# Sheet3.net
KiCad netlist of a schematic drawn in Altium Designer
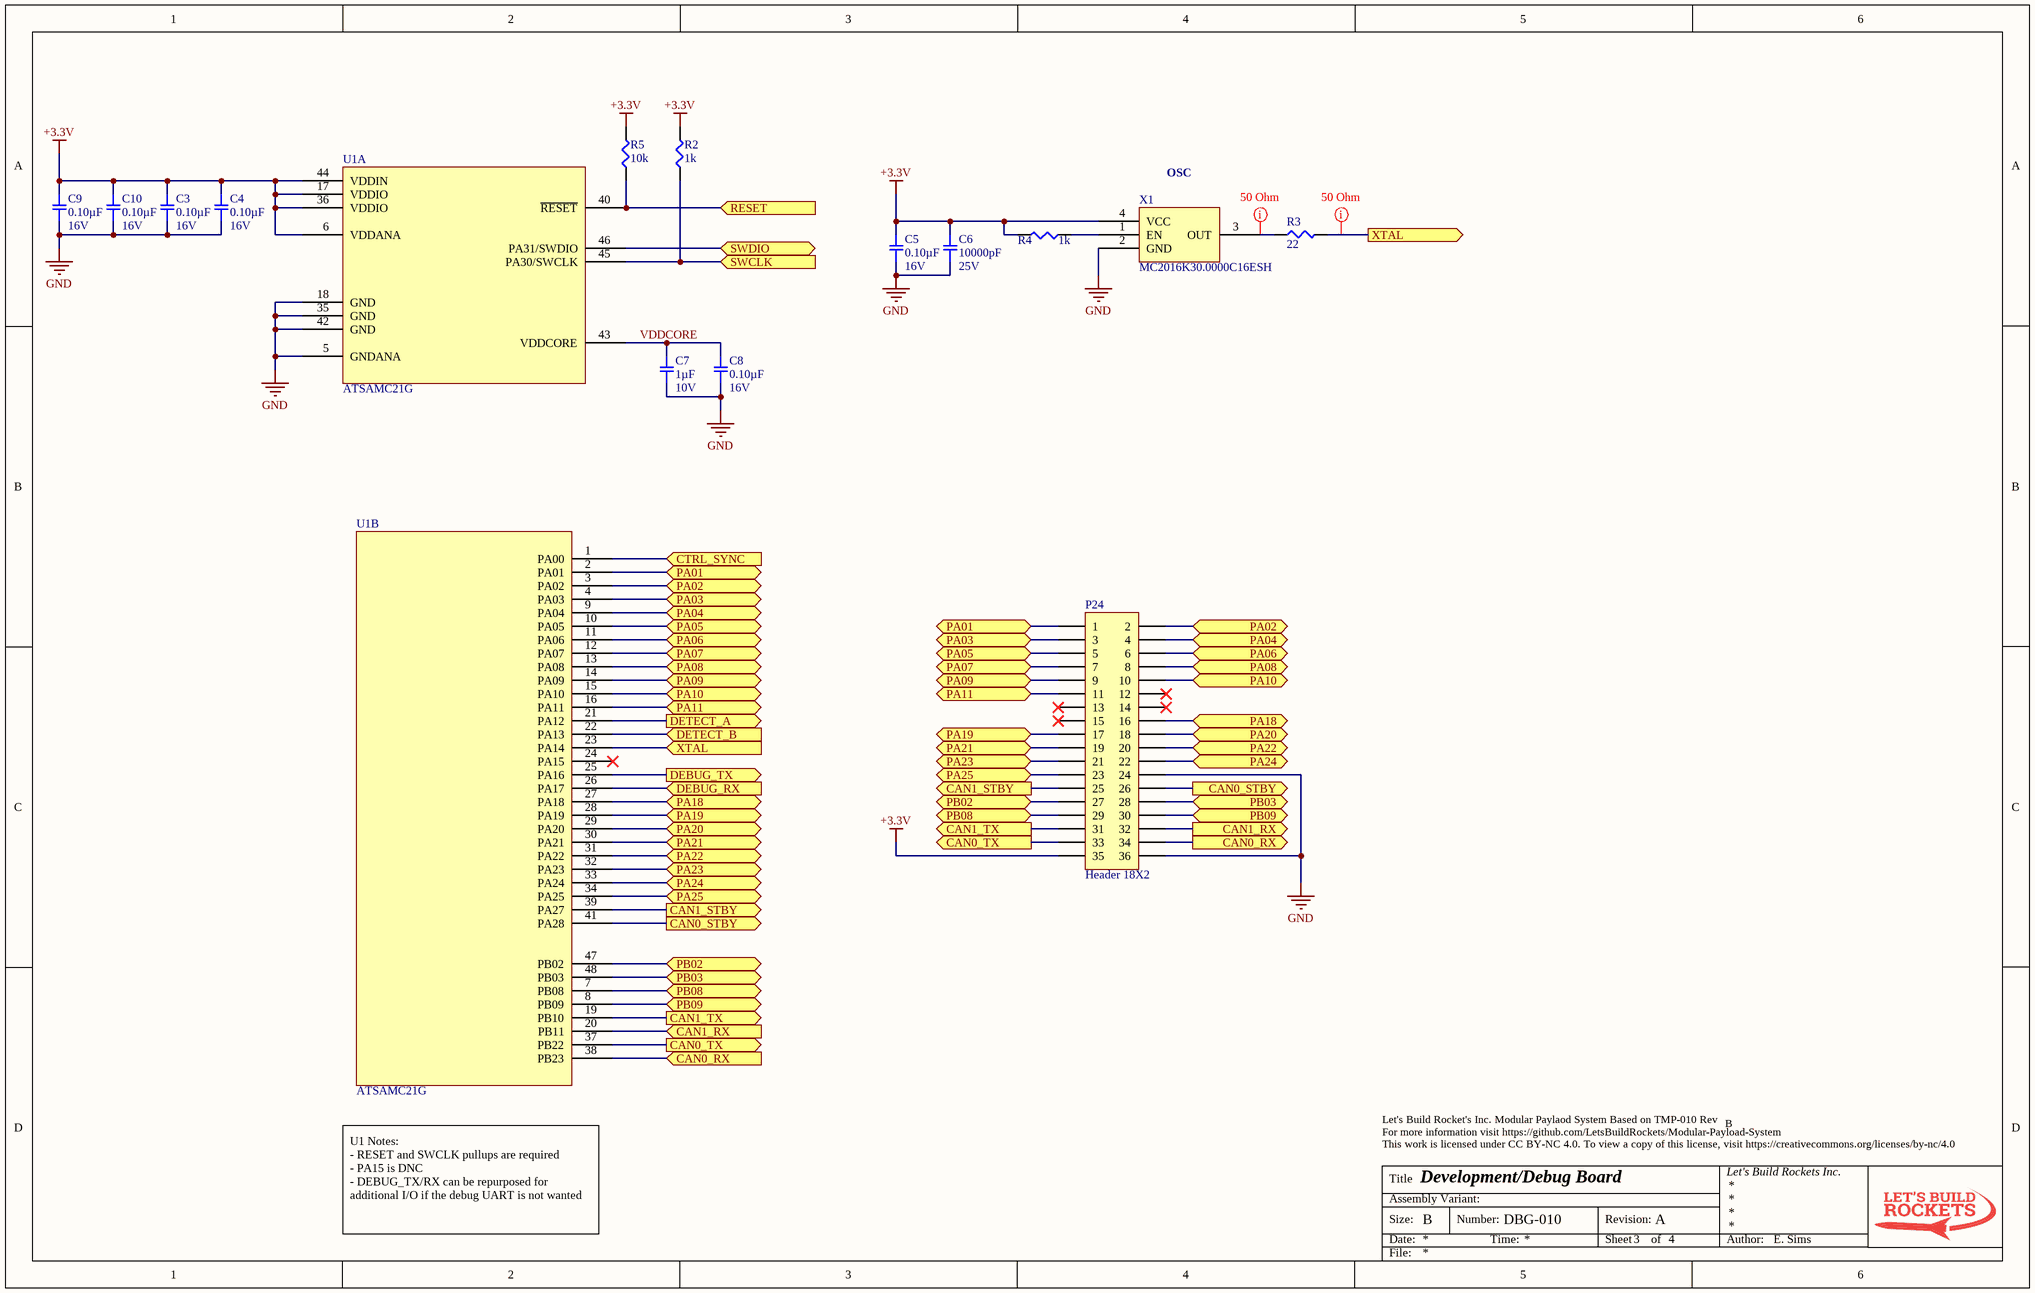
[diagram p0: Sheet3.SchDoc]

(export (version "E")
  (design (tool "Eeschema 10.0.6"))
  (components
    (comp (ref "C3")
      (value "0.10µF")
      (footprint "SMD-0402C")
      (description "CAP CER 0.1UF 16V X7R 0402")
      (fields
        (field (name "DIGI-KEY PART NUMBER") "490-4759-1-ND")
        (field (name "PART NUMBER") "GCM155R71C104KA55D")
        (field (name "VOLTAGE") "16V")
      )
      (libsource (lib "capacitor_murata_0402") (part "GCM155R71C104KA55D"))
    )
    (comp (ref "C4")
      (value "0.10µF")
      (footprint "SMD-0402C")
      (description "CAP CER 0.1UF 16V X7R 0402")
      (fields
        (field (name "DIGI-KEY PART NUMBER") "490-4759-1-ND")
        (field (name "PART NUMBER") "GCM155R71C104KA55D")
        (field (name "VOLTAGE") "16V")
      )
      (libsource (lib "capacitor_murata_0402") (part "GCM155R71C104KA55D"))
    )
    (comp (ref "C5")
      (value "0.10µF")
      (footprint "SMD-0402C")
      (description "CAP CER 0.1UF 16V X7R 0402")
      (fields
        (field (name "DIGI-KEY PART NUMBER") "490-4759-1-ND")
        (field (name "PART NUMBER") "GCM155R71C104KA55D")
        (field (name "VOLTAGE") "16V")
      )
      (libsource (lib "capacitor_murata_0402") (part "GCM155R71C104KA55D"))
    )
    (comp (ref "C6")
      (value "10000pF")
      (footprint "SMD-0402C")
      (description "CAP CER 10000PF 25V X7R 0402")
      (fields
        (field (name "DIGI-KEY PART NUMBER") "490-6043-1-ND")
        (field (name "PART NUMBER") "GCM155R71E103KA37D")
        (field (name "VOLTAGE") "25V")
      )
      (libsource (lib "capacitor_murata_0402") (part "GCM155R71E103KA37D"))
    )
    (comp (ref "C7")
      (value "1µF")
      (footprint "SMD-0402C")
      (description "CAP CER 1UF 10V X7S 0402")
      (fields
        (field (name "DIGI-KEY PART NUMBER") "490-13409-1-ND")
        (field (name "PART NUMBER") "GCM155C71A105KE38D")
        (field (name "VOLTAGE") "10V")
      )
      (libsource (lib "capacitor_murata_0402") (part "GCM155C71A105KE38D"))
    )
    (comp (ref "C8")
      (value "0.10µF")
      (footprint "SMD-0402C")
      (description "CAP CER 0.1UF 16V X7R 0402")
      (fields
        (field (name "DIGI-KEY PART NUMBER") "490-4759-1-ND")
        (field (name "PART NUMBER") "GCM155R71C104KA55D")
        (field (name "VOLTAGE") "16V")
      )
      (libsource (lib "capacitor_murata_0402") (part "GCM155R71C104KA55D"))
    )
    (comp (ref "C9")
      (value "0.10µF")
      (footprint "SMD-0402C")
      (description "CAP CER 0.1UF 16V X7R 0402")
      (fields
        (field (name "DIGI-KEY PART NUMBER") "490-4759-1-ND")
        (field (name "PART NUMBER") "GCM155R71C104KA55D")
        (field (name "VOLTAGE") "16V")
      )
      (libsource (lib "capacitor_murata_0402") (part "GCM155R71C104KA55D"))
    )
    (comp (ref "C10")
      (value "0.10µF")
      (footprint "SMD-0402C")
      (description "CAP CER 0.1UF 16V X7R 0402")
      (fields
        (field (name "DIGI-KEY PART NUMBER") "490-4759-1-ND")
        (field (name "PART NUMBER") "GCM155R71C104KA55D")
        (field (name "VOLTAGE") "16V")
      )
      (libsource (lib "capacitor_murata_0402") (part "GCM155R71C104KA55D"))
    )
    (comp (ref "P24")
      (value "Header 18X2")
      (footprint "HDR2X18")
      (description "Header, 18-Pin, Dual row")
      (fields (field (name "PUBLISHER") "Altium Limited"))
      (libsource (lib "Miscellaneous Connectors") (part "Header 18X2"))
    )
    (comp (ref "R2")
      (value "1k")
      (footprint "SMD-0402-RES")
      (description "RES SMD 1K OHM 5% 1/10W 0402")
      (fields (field (name "PART NUMBER") "ERJ-2GEJ102X") (field (name "DIGI-KEY PART NUMBER") "P1.0KJCT-ND"))
      (libsource (lib "Panasonic_ERJ_0402") (part "ERJ-2GEJ102X"))
    )
    (comp (ref "R3")
      (value "22")
      (footprint "SMD-0402-RES")
      (description "RES SMD 22 OHM 1% 1/10W 0402")
      (fields
        (field (name "PART NUMBER") "ERJ-2RKF22R0X")
        (field (name "DIGI-KEY PART NUMBER") "P22.0LCT-ND")
      )
      (libsource (lib "Panasonic_ERJ_0402") (part "ERJ-2RKF22R0X"))
    )
    (comp (ref "R4")
      (value "1k")
      (footprint "SMD-0402-RES")
      (description "RES SMD 1K OHM 5% 1/10W 0402")
      (fields (field (name "PART NUMBER") "ERJ-2GEJ102X") (field (name "DIGI-KEY PART NUMBER") "P1.0KJCT-ND"))
      (libsource (lib "Panasonic_ERJ_0402") (part "ERJ-2GEJ102X"))
    )
    (comp (ref "R5")
      (value "10k")
      (footprint "SMD-0402-RES")
      (description "RES SMD 10K OHM 5% 1/10W 0402")
      (fields (field (name "PART NUMBER") "ERJ-2GEJ103X") (field (name "DIGI-KEY PART NUMBER") "P10KJCT-ND"))
      (libsource (lib "Panasonic_ERJ_0402") (part "ERJ-2GEJ103X"))
    )
    (comp (ref "U1")
      (value "ATSAMC21G")
      (footprint "TSQFP50P900X900X120-48N")
      (libsource (lib "ModularPayload") (part "ATSAMC21G"))
    )
    (comp (ref "X1")
      (value "MC2016K30.0000C16ESH")
      (footprint "MC2016")
      (libsource (lib "ModularPayload") (part "MC2016K30.0000C16ESH"))
    )
  )
  (nets
    (net (code "1") (name "+3.3V") (class "Default")
      (node (ref "C10") (pin "2") (pinfunction "2_2") (pintype "passive"))
      (node (ref "C3") (pin "2") (pinfunction "2_2") (pintype "passive"))
      (node (ref "C4") (pin "2") (pinfunction "2_2") (pintype "passive"))
      (node (ref "C5") (pin "2") (pinfunction "2_2") (pintype "passive"))
      (node (ref "C6") (pin "2") (pinfunction "2_2") (pintype "passive"))
      (node (ref "C9") (pin "2") (pinfunction "2_2") (pintype "passive"))
      (node (ref "P24") (pin "35") (pinfunction "35_35") (pintype "passive"))
      (node (ref "R2") (pin "2") (pinfunction "2_2") (pintype "passive"))
      (node (ref "R4") (pin "2") (pinfunction "2_2") (pintype "passive"))
      (node (ref "R5") (pin "2") (pinfunction "2_2") (pintype "passive"))
      (node (ref "U1") (pin "17") (pinfunction "VDDIO_17") (pintype "passive"))
      (node (ref "U1") (pin "36") (pinfunction "VDDIO_36") (pintype "passive"))
      (node (ref "U1") (pin "44") (pinfunction "VDDIN_44") (pintype "passive"))
      (node (ref "U1") (pin "6") (pinfunction "VDDANA_6") (pintype "passive"))
      (node (ref "X1") (pin "4") (pinfunction "VCC_4") (pintype "passive"))
    )
    (net (code "2") (name "/CAN0_RX") (class "Default")
      (node (ref "P24") (pin "34") (pinfunction "34_34") (pintype "passive"))
      (node (ref "U1") (pin "38") (pinfunction "PB23_38") (pintype "passive"))
    )
    (net (code "3") (name "/CAN0_STBY") (class "Default")
      (node (ref "P24") (pin "26") (pinfunction "26_26") (pintype "passive"))
      (node (ref "U1") (pin "41") (pinfunction "PA28_41") (pintype "passive"))
    )
    (net (code "4") (name "/CAN0_TX") (class "Default")
      (node (ref "P24") (pin "33") (pinfunction "33_33") (pintype "passive"))
      (node (ref "U1") (pin "37") (pinfunction "PB22_37") (pintype "passive"))
    )
    (net (code "5") (name "/CAN1_RX") (class "Default")
      (node (ref "P24") (pin "32") (pinfunction "32_32") (pintype "passive"))
      (node (ref "U1") (pin "20") (pinfunction "PB11_20") (pintype "passive"))
    )
    (net (code "6") (name "/CAN1_STBY") (class "Default")
      (node (ref "P24") (pin "25") (pinfunction "25_25") (pintype "passive"))
      (node (ref "U1") (pin "39") (pinfunction "PA27_39") (pintype "passive"))
    )
    (net (code "7") (name "/CAN1_TX") (class "Default")
      (node (ref "P24") (pin "31") (pinfunction "31_31") (pintype "passive"))
      (node (ref "U1") (pin "19") (pinfunction "PB10_19") (pintype "passive"))
    )
    (net (code "8") (name "/CTRL_SYNC") (class "Default")
      (node (ref "U1") (pin "1") (pinfunction "PA00_1") (pintype "passive"))
    )
    (net (code "9") (name "/DEBUG_RX") (class "Default")
      (node (ref "U1") (pin "26") (pinfunction "PA17_26") (pintype "passive"))
    )
    (net (code "10") (name "/DEBUG_TX") (class "Default")
      (node (ref "U1") (pin "25") (pinfunction "PA16_25") (pintype "passive"))
    )
    (net (code "11") (name "/DETECT_A") (class "Default")
      (node (ref "U1") (pin "21") (pinfunction "PA12_21") (pintype "passive"))
    )
    (net (code "12") (name "/DETECT_B") (class "Default")
      (node (ref "U1") (pin "22") (pinfunction "PA13_22") (pintype "passive"))
    )
    (net (code "13") (name "/PA01") (class "Default")
      (node (ref "P24") (pin "1") (pinfunction "1_1") (pintype "passive"))
      (node (ref "U1") (pin "2") (pinfunction "PA01_2") (pintype "passive"))
    )
    (net (code "14") (name "/PA02") (class "Default")
      (node (ref "P24") (pin "2") (pinfunction "2_2") (pintype "passive"))
      (node (ref "U1") (pin "3") (pinfunction "PA02_3") (pintype "passive"))
    )
    (net (code "15") (name "/PA03") (class "Default")
      (node (ref "P24") (pin "3") (pinfunction "3_3") (pintype "passive"))
      (node (ref "U1") (pin "4") (pinfunction "PA03_4") (pintype "passive"))
    )
    (net (code "16") (name "/PA04") (class "Default")
      (node (ref "P24") (pin "4") (pinfunction "4_4") (pintype "passive"))
      (node (ref "U1") (pin "9") (pinfunction "PA04_9") (pintype "passive"))
    )
    (net (code "17") (name "/PA05") (class "Default")
      (node (ref "P24") (pin "5") (pinfunction "5_5") (pintype "passive"))
      (node (ref "U1") (pin "10") (pinfunction "PA05_10") (pintype "passive"))
    )
    (net (code "18") (name "/PA06") (class "Default")
      (node (ref "P24") (pin "6") (pinfunction "6_6") (pintype "passive"))
      (node (ref "U1") (pin "11") (pinfunction "PA06_11") (pintype "passive"))
    )
    (net (code "19") (name "/PA07") (class "Default")
      (node (ref "P24") (pin "7") (pinfunction "7_7") (pintype "passive"))
      (node (ref "U1") (pin "12") (pinfunction "PA07_12") (pintype "passive"))
    )
    (net (code "20") (name "/PA08") (class "Default")
      (node (ref "P24") (pin "8") (pinfunction "8_8") (pintype "passive"))
      (node (ref "U1") (pin "13") (pinfunction "PA08_13") (pintype "passive"))
    )
    (net (code "21") (name "/PA09") (class "Default")
      (node (ref "P24") (pin "9") (pinfunction "9_9") (pintype "passive"))
      (node (ref "U1") (pin "14") (pinfunction "PA09_14") (pintype "passive"))
    )
    (net (code "22") (name "/PA10") (class "Default")
      (node (ref "P24") (pin "10") (pinfunction "10_10") (pintype "passive"))
      (node (ref "U1") (pin "15") (pinfunction "PA10_15") (pintype "passive"))
    )
    (net (code "23") (name "/PA11") (class "Default")
      (node (ref "P24") (pin "11") (pinfunction "11_11") (pintype "passive"))
      (node (ref "U1") (pin "16") (pinfunction "PA11_16") (pintype "passive"))
    )
    (net (code "24") (name "/PA18") (class "Default")
      (node (ref "P24") (pin "16") (pinfunction "16_16") (pintype "passive"))
      (node (ref "U1") (pin "27") (pinfunction "PA18_27") (pintype "passive"))
    )
    (net (code "25") (name "/PA19") (class "Default")
      (node (ref "P24") (pin "17") (pinfunction "17_17") (pintype "passive"))
      (node (ref "U1") (pin "28") (pinfunction "PA19_28") (pintype "passive"))
    )
    (net (code "26") (name "/PA20") (class "Default")
      (node (ref "P24") (pin "18") (pinfunction "18_18") (pintype "passive"))
      (node (ref "U1") (pin "29") (pinfunction "PA20_29") (pintype "passive"))
    )
    (net (code "27") (name "/PA21") (class "Default")
      (node (ref "P24") (pin "19") (pinfunction "19_19") (pintype "passive"))
      (node (ref "U1") (pin "30") (pinfunction "PA21_30") (pintype "passive"))
    )
    (net (code "28") (name "/PA22") (class "Default")
      (node (ref "P24") (pin "20") (pinfunction "20_20") (pintype "passive"))
      (node (ref "U1") (pin "31") (pinfunction "PA22_31") (pintype "passive"))
    )
    (net (code "29") (name "/PA23") (class "Default")
      (node (ref "P24") (pin "21") (pinfunction "21_21") (pintype "passive"))
      (node (ref "U1") (pin "32") (pinfunction "PA23_32") (pintype "passive"))
    )
    (net (code "30") (name "/PA24") (class "Default")
      (node (ref "P24") (pin "22") (pinfunction "22_22") (pintype "passive"))
      (node (ref "U1") (pin "33") (pinfunction "PA24_33") (pintype "passive"))
    )
    (net (code "31") (name "/PA25") (class "Default")
      (node (ref "P24") (pin "23") (pinfunction "23_23") (pintype "passive"))
      (node (ref "U1") (pin "34") (pinfunction "PA25_34") (pintype "passive"))
    )
    (net (code "32") (name "/PB02") (class "Default")
      (node (ref "P24") (pin "27") (pinfunction "27_27") (pintype "passive"))
      (node (ref "U1") (pin "47") (pinfunction "PB02_47") (pintype "passive"))
    )
    (net (code "33") (name "/PB03") (class "Default")
      (node (ref "P24") (pin "28") (pinfunction "28_28") (pintype "passive"))
      (node (ref "U1") (pin "48") (pinfunction "PB03_48") (pintype "passive"))
    )
    (net (code "34") (name "/PB08") (class "Default")
      (node (ref "P24") (pin "29") (pinfunction "29_29") (pintype "passive"))
      (node (ref "U1") (pin "7") (pinfunction "PB08_7") (pintype "passive"))
    )
    (net (code "35") (name "/PB09") (class "Default")
      (node (ref "P24") (pin "30") (pinfunction "30_30") (pintype "passive"))
      (node (ref "U1") (pin "8") (pinfunction "PB09_8") (pintype "passive"))
    )
    (net (code "36") (name "/RESET") (class "Default")
      (node (ref "R5") (pin "1") (pinfunction "1_1") (pintype "passive"))
      (node (ref "U1") (pin "40") (pinfunction "~{RESET}_40") (pintype "passive"))
    )
    (net (code "37") (name "/SWCLK") (class "Default")
      (node (ref "R2") (pin "1") (pinfunction "1_1") (pintype "passive"))
      (node (ref "U1") (pin "45") (pinfunction "PA30/SWCLK_45") (pintype "passive"))
    )
    (net (code "38") (name "/SWDIO") (class "Default")
      (node (ref "U1") (pin "46") (pinfunction "PA31/SWDIO_46") (pintype "passive"))
    )
    (net (code "39") (name "/VDDCORE") (class "Default")
      (node (ref "C7") (pin "2") (pinfunction "2_2") (pintype "passive"))
      (node (ref "C8") (pin "2") (pinfunction "2_2") (pintype "passive"))
      (node (ref "U1") (pin "43") (pinfunction "VDDCORE_43") (pintype "passive"))
    )
    (net (code "40") (name "/XTAL") (class "Default")
      (node (ref "R3") (pin "2") (pinfunction "2_2") (pintype "passive"))
      (node (ref "U1") (pin "23") (pinfunction "PA14_23") (pintype "passive"))
    )
    (net (code "41") (name "GND") (class "Default")
      (node (ref "C10") (pin "1") (pinfunction "1_1") (pintype "passive"))
      (node (ref "C3") (pin "1") (pinfunction "1_1") (pintype "passive"))
      (node (ref "C4") (pin "1") (pinfunction "1_1") (pintype "passive"))
      (node (ref "C5") (pin "1") (pinfunction "1_1") (pintype "passive"))
      (node (ref "C6") (pin "1") (pinfunction "1_1") (pintype "passive"))
      (node (ref "C7") (pin "1") (pinfunction "1_1") (pintype "passive"))
      (node (ref "C8") (pin "1") (pinfunction "1_1") (pintype "passive"))
      (node (ref "C9") (pin "1") (pinfunction "1_1") (pintype "passive"))
      (node (ref "P24") (pin "24") (pinfunction "24_24") (pintype "passive"))
      (node (ref "P24") (pin "36") (pinfunction "36_36") (pintype "passive"))
      (node (ref "U1") (pin "18") (pinfunction "GND_18") (pintype "passive"))
      (node (ref "U1") (pin "35") (pinfunction "GND_35") (pintype "passive"))
      (node (ref "U1") (pin "42") (pinfunction "GND_42") (pintype "passive"))
      (node (ref "U1") (pin "5") (pinfunction "GNDANA_5") (pintype "passive"))
      (node (ref "X1") (pin "2") (pinfunction "GND_2") (pintype "passive"))
    )
    (net (code "42") (name "Net-(X1-EN)") (class "Default")
      (node (ref "R4") (pin "1") (pinfunction "1_1") (pintype "passive"))
      (node (ref "X1") (pin "1") (pinfunction "EN_1") (pintype "passive"))
    )
    (net (code "43") (name "Net-(X1-OUT)") (class "Default")
      (node (ref "R3") (pin "1") (pinfunction "1_1") (pintype "passive"))
      (node (ref "X1") (pin "3") (pinfunction "OUT_3") (pintype "passive"))
    )
    (net (code "44") (name "unconnected-(P24-Pad12)") (class "Default")
      (node (ref "P24") (pin "12") (pinfunction "12_12") (pintype "passive+no_connect"))
    )
    (net (code "45") (name "unconnected-(P24-Pad13)") (class "Default")
      (node (ref "P24") (pin "13") (pinfunction "13_13") (pintype "passive+no_connect"))
    )
    (net (code "46") (name "unconnected-(P24-Pad14)") (class "Default")
      (node (ref "P24") (pin "14") (pinfunction "14_14") (pintype "passive+no_connect"))
    )
    (net (code "47") (name "unconnected-(P24-Pad15)") (class "Default")
      (node (ref "P24") (pin "15") (pinfunction "15_15") (pintype "passive+no_connect"))
    )
    (net (code "48") (name "unconnected-(U1B-PA15-Pad24)") (class "Default")
      (node (ref "U1") (pin "24") (pinfunction "PA15_24") (pintype "passive+no_connect"))
    )
  )
)
